# pack.net
KiCad netlist of a schematic drawn in EasyEDA Pro
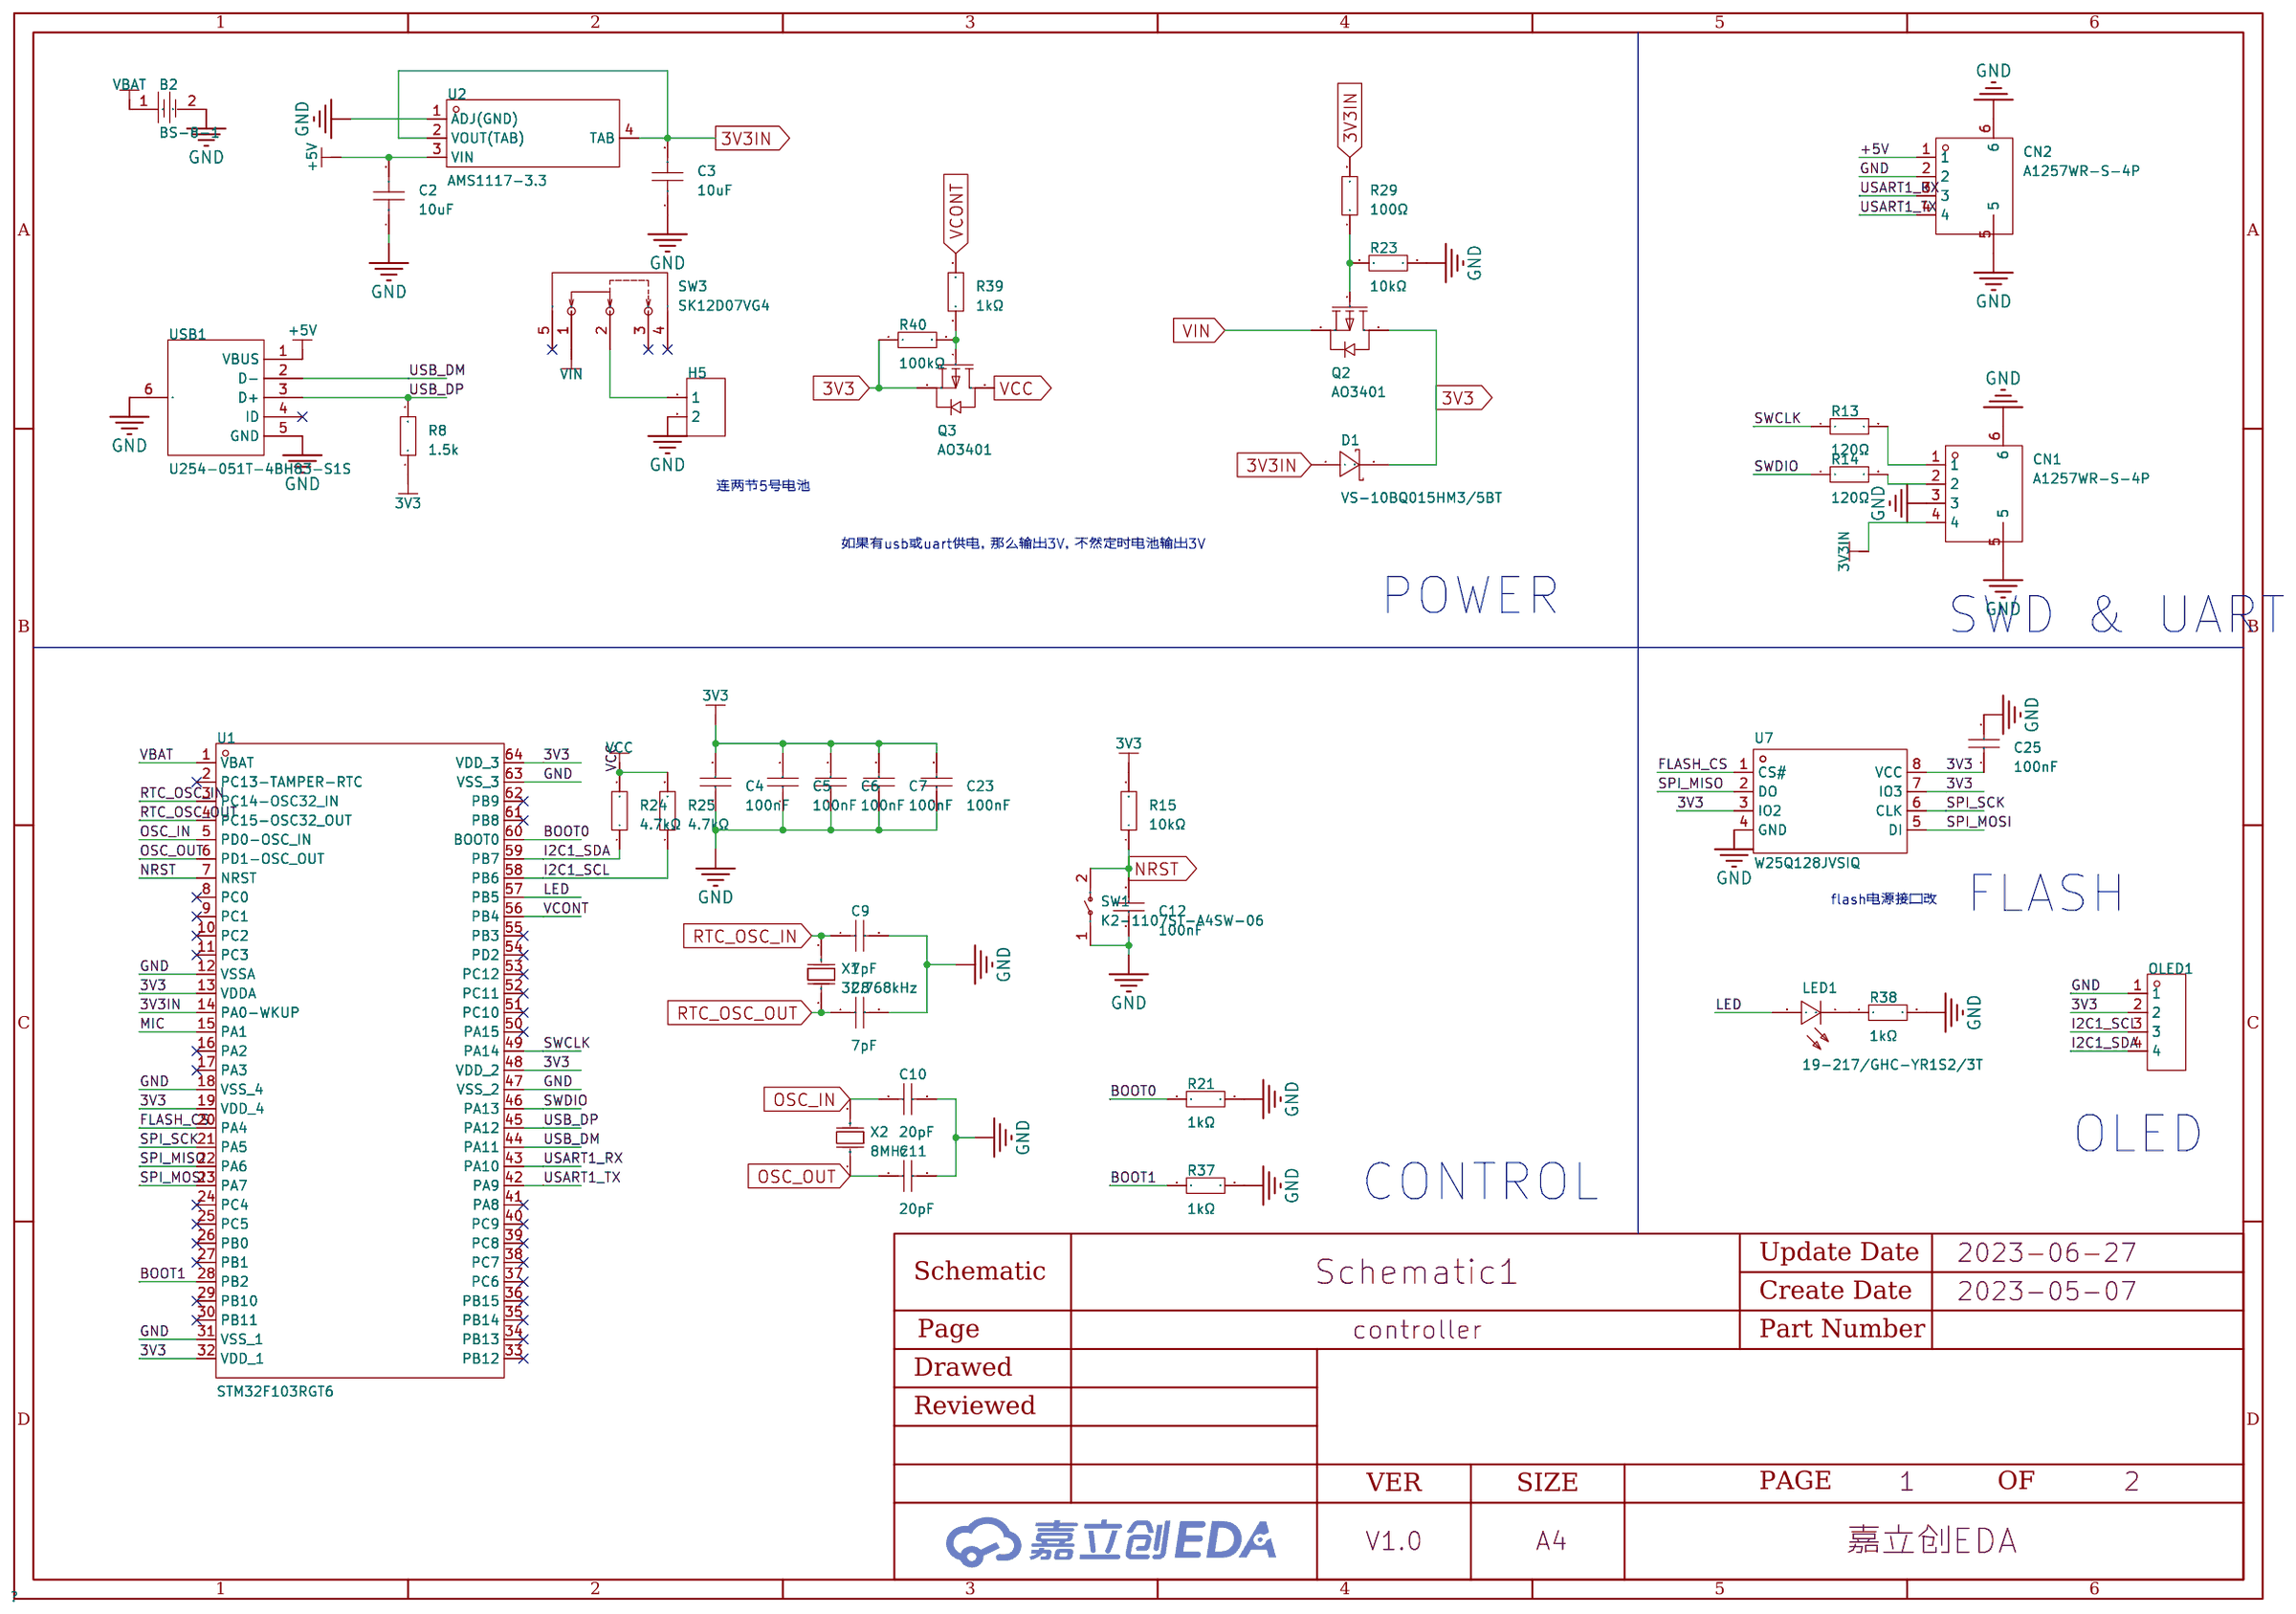
[diagram p0: controller]
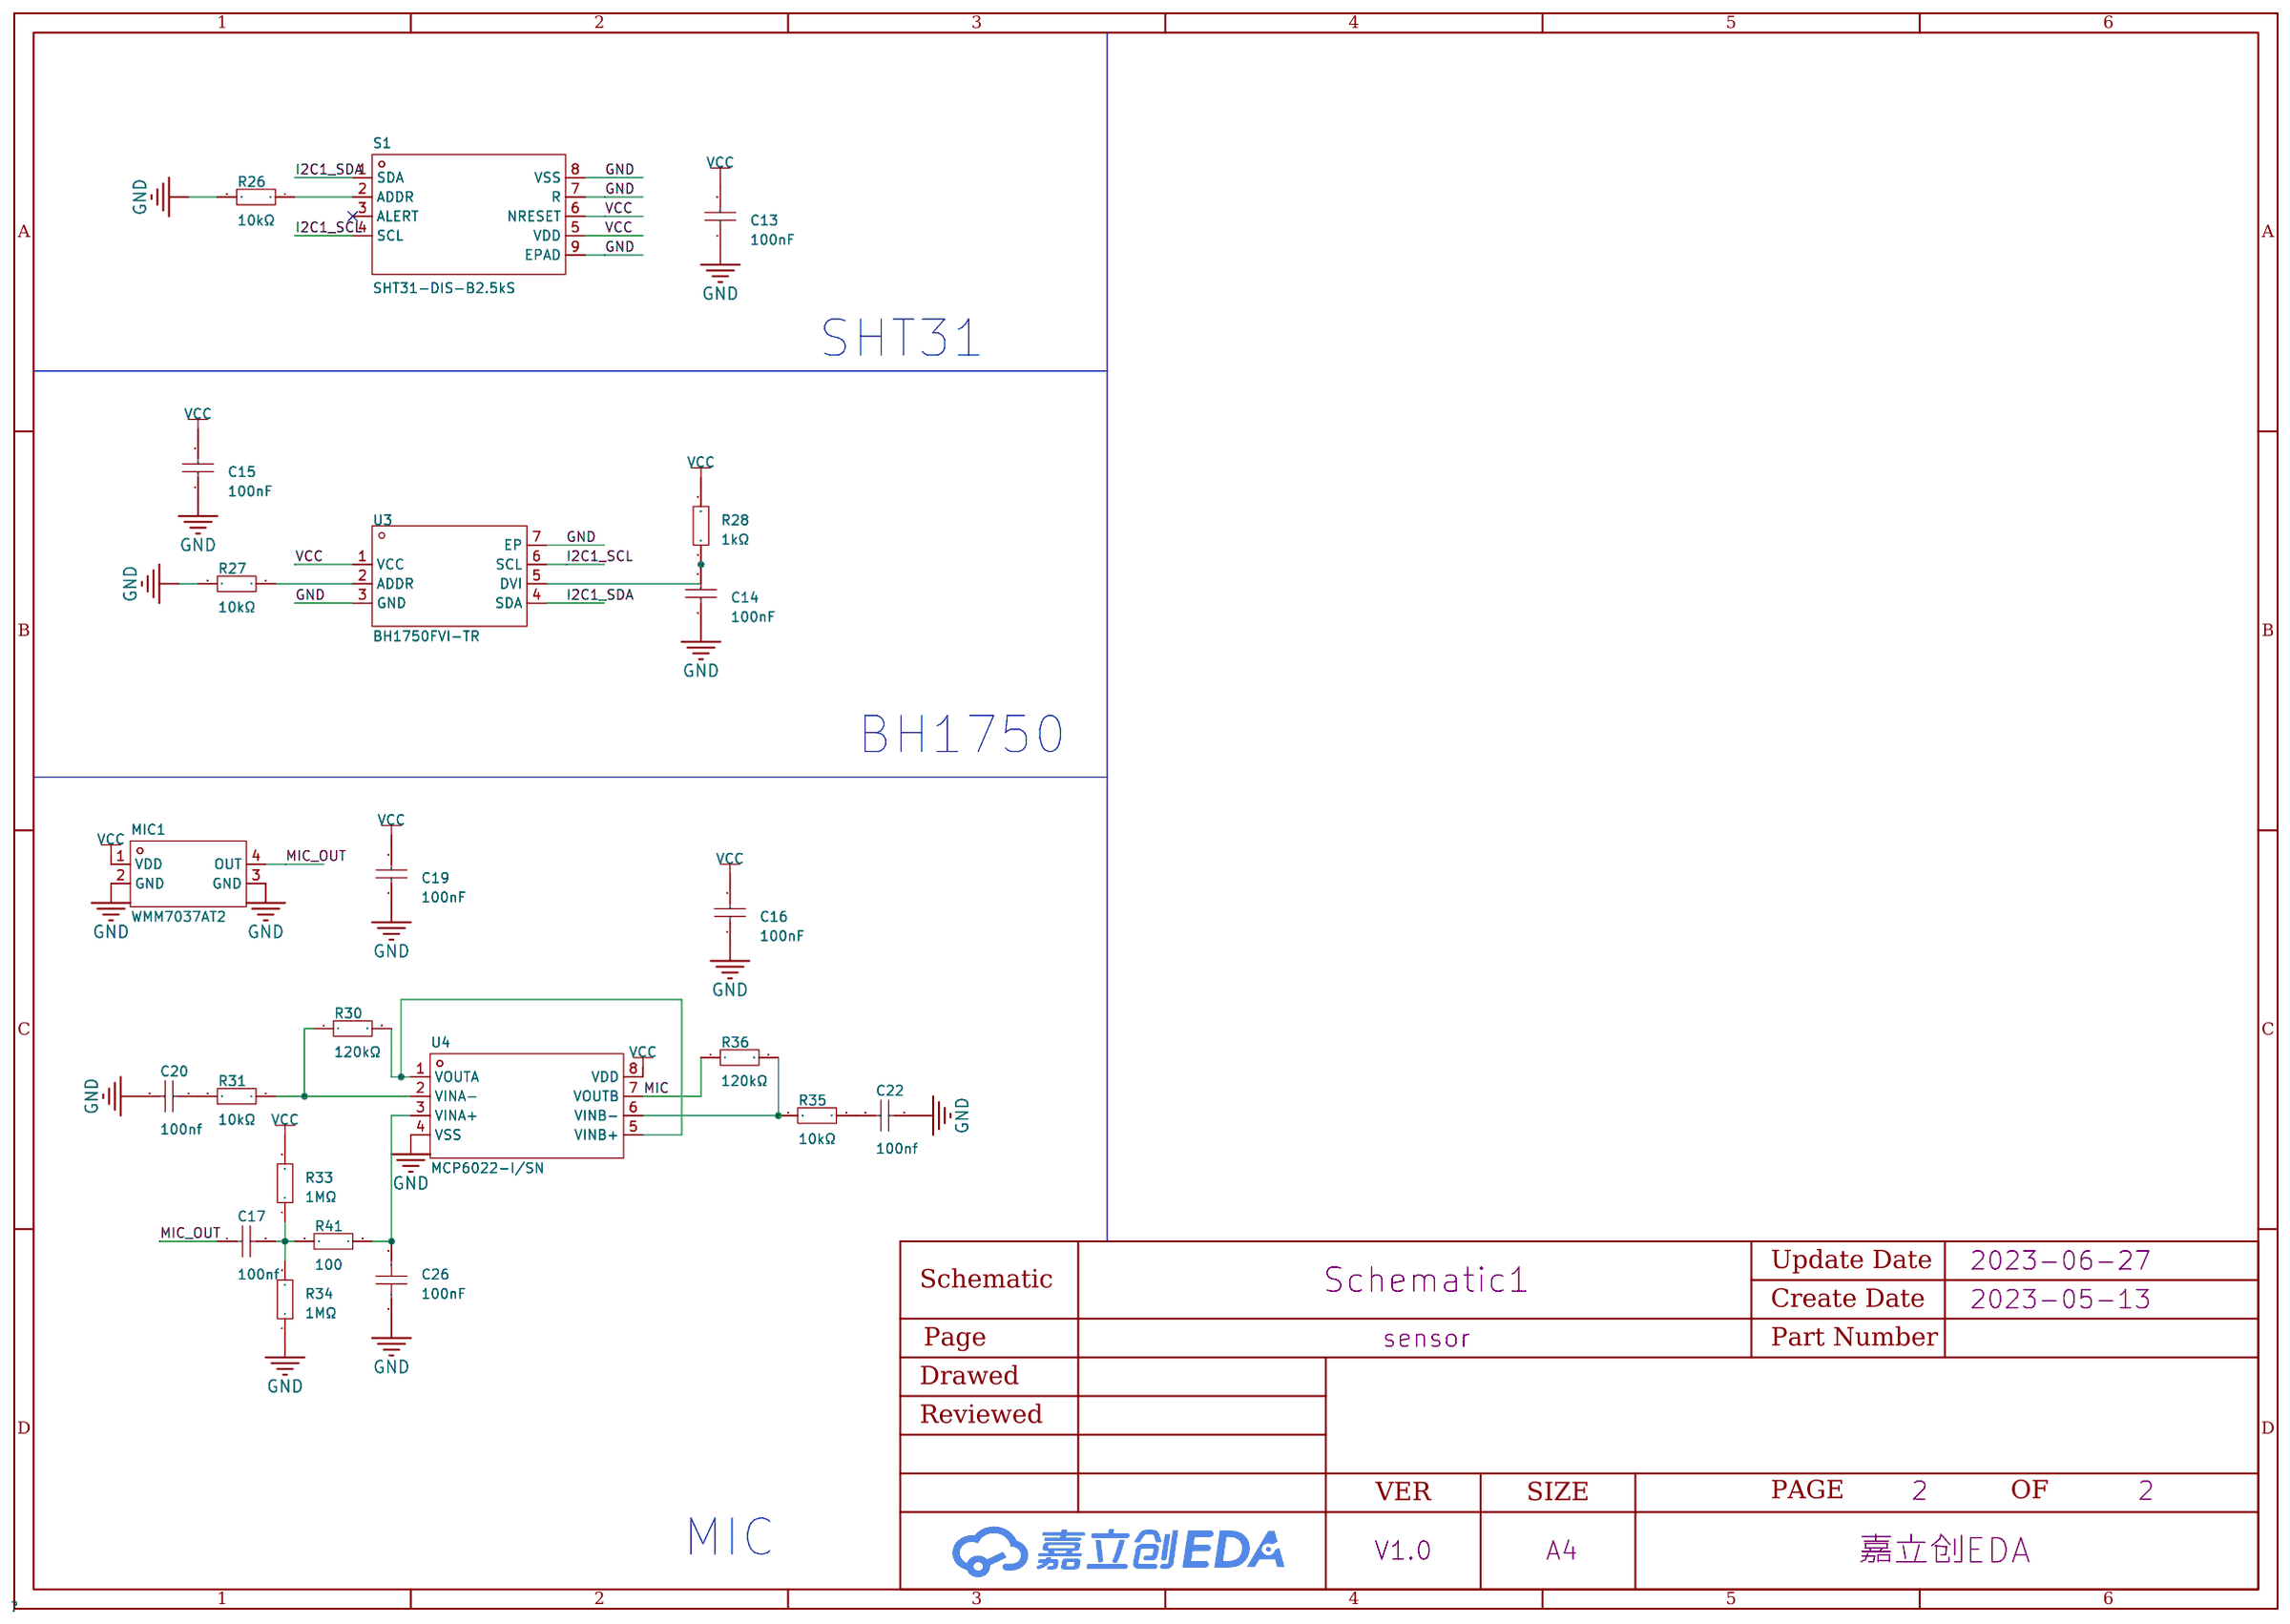
[diagram p1: sensor]

(export (version "E")
  (design (tool "Eeschema 10.0.6"))
  (components
    (comp (ref "B2")
      (value "BS-8-1")
      (footprint "easyedapro:BAT-TH_BS-8-1")
      (description "连接器类型:电池底座;适用电池规格:CR2032;工作温度范围:-55°C~+85°C;")
      (fields (field (name "Manufacturer") "Q&J"))
      (libsource (lib "easyedapro") (part "CR2032-BS-8-1"))
    )
    (comp (ref "C2")
      (value "10uF")
      (footprint "easyedapro:C0603")
      (description "容值:10uF;精度:±20%;额定电压:25V;材质(温度系数):X5R;")
      (fields
        (field (name "Manufacturer Part") "CL10A106MA8NRNC")
        (field (name "Manufacturer") "SAMSUNG(三星)")
      )
      (libsource (lib "easyedapro") (part "CL10A106MA8NRNC"))
    )
    (comp (ref "C3")
      (value "10uF")
      (footprint "easyedapro:C0603")
      (description "容值:10uF;精度:±20%;额定电压:25V;材质(温度系数):X5R;")
      (fields
        (field (name "Manufacturer Part") "CL10A106MA8NRNC")
        (field (name "Manufacturer") "SAMSUNG(三星)")
      )
      (libsource (lib "easyedapro") (part "CL10A106MA8NRNC"))
    )
    (comp (ref "C4")
      (value "100nF")
      (footprint "easyedapro:C0603")
      (description "容值:100nF;精度:±10%;额定电压:50V;材质(温度系数):X7R;")
      (fields (field (name "Manufacturer Part") "0603B104K500NT") (field (name "Manufacturer") "FH(风华)"))
      (libsource (lib "easyedapro") (part "0603B104K500NT"))
    )
    (comp (ref "C5")
      (value "100nF")
      (footprint "easyedapro:C0603")
      (description "容值:100nF;精度:±10%;额定电压:50V;材质(温度系数):X7R;")
      (fields (field (name "Manufacturer Part") "0603B104K500NT") (field (name "Manufacturer") "FH(风华)"))
      (libsource (lib "easyedapro") (part "0603B104K500NT"))
    )
    (comp (ref "C6")
      (value "100nF")
      (footprint "easyedapro:C0603")
      (description "容值:100nF;精度:±10%;额定电压:50V;材质(温度系数):X7R;")
      (fields (field (name "Manufacturer Part") "0603B104K500NT") (field (name "Manufacturer") "FH(风华)"))
      (libsource (lib "easyedapro") (part "0603B104K500NT"))
    )
    (comp (ref "C7")
      (value "100nF")
      (footprint "easyedapro:C0603")
      (description "容值:100nF;精度:±10%;额定电压:50V;材质(温度系数):X7R;")
      (fields (field (name "Manufacturer Part") "0603B104K500NT") (field (name "Manufacturer") "FH(风华)"))
      (libsource (lib "easyedapro") (part "0603B104K500NT"))
    )
    (comp (ref "C8")
      (value "7pF")
      (footprint "easyedapro:C0603")
      (description "容值:7pF;额定电压:50V;材质(温度系数):C0G;")
      (fields (field (name "Manufacturer Part") "0603CG7R0C500NT") (field (name "Manufacturer") "FH(风华)"))
      (libsource (lib "easyedapro") (part "0603CG7R0C500NT"))
    )
    (comp (ref "C9")
      (value "7pF")
      (footprint "easyedapro:C0603")
      (description "容值:7pF;额定电压:50V;材质(温度系数):C0G;")
      (fields (field (name "Manufacturer Part") "0603CG7R0C500NT") (field (name "Manufacturer") "FH(风华)"))
      (libsource (lib "easyedapro") (part "0603CG7R0C500NT"))
    )
    (comp (ref "C10")
      (value "20pF")
      (footprint "easyedapro:C0603")
      (description "容值:20pF;精度:±5%;额定电压:50V;材质(温度系数):C0G;")
      (fields
        (field (name "Manufacturer Part") "CL10C200JB8NNNC")
        (field (name "Manufacturer") "SAMSUNG(三星)")
      )
      (libsource (lib "easyedapro") (part "CL10C200JB8NNNC"))
    )
    (comp (ref "C11")
      (value "20pF")
      (footprint "easyedapro:C0603")
      (description "容值:20pF;精度:±5%;额定电压:50V;材质(温度系数):C0G;")
      (fields
        (field (name "Manufacturer Part") "CL10C200JB8NNNC")
        (field (name "Manufacturer") "SAMSUNG(三星)")
      )
      (libsource (lib "easyedapro") (part "CL10C200JB8NNNC"))
    )
    (comp (ref "C12")
      (value "100nF")
      (footprint "easyedapro:C0603")
      (description "容值:100nF;精度:±10%;额定电压:50V;材质(温度系数):X7R;")
      (fields (field (name "Manufacturer Part") "0603B104K500NT") (field (name "Manufacturer") "FH(风华)"))
      (libsource (lib "easyedapro") (part "0603B104K500NT"))
    )
    (comp (ref "C23")
      (value "100nF")
      (footprint "easyedapro:C0603")
      (description "容值:100nF;精度:±10%;额定电压:50V;材质(温度系数):X7R;")
      (fields (field (name "Manufacturer Part") "0603B104K500NT") (field (name "Manufacturer") "FH(风华)"))
      (libsource (lib "easyedapro") (part "0603B104K500NT"))
    )
    (comp (ref "C25")
      (value "100nF")
      (footprint "easyedapro:C0603")
      (description "容值:100nF;精度:±10%;额定电压:50V;材质(温度系数):X7R;")
      (fields (field (name "Manufacturer Part") "0603B104K500NT") (field (name "Manufacturer") "FH(风华)"))
      (libsource (lib "easyedapro") (part "0603B104K500NT"))
    )
    (comp (ref "CN1")
      (value "A1257WR-S-4P")
      (footprint "easyedapro:CONN-SMD_A1257WR-S-4P")
      (description "参考系列:GH;间距:1.25mm;插针结构:1x4P;排数:1;每排PIN数:4;行距:-;安装方式:-;触头材质:黄铜;")
      (fields (field (name "Manufacturer") "CJT(长江连接器)"))
      (libsource (lib "easyedapro") (part "A1257WR-S-4P"))
    )
    (comp (ref "CN2")
      (value "A1257WR-S-4P")
      (footprint "easyedapro:CONN-SMD_A1257WR-S-4P")
      (description "参考系列:GH;间距:1.25mm;插针结构:1x4P;排数:1;每排PIN数:4;行距:-;安装方式:-;触头材质:黄铜;")
      (fields (field (name "Manufacturer") "CJT(长江连接器)"))
      (libsource (lib "easyedapro") (part "A1257WR-S-4P"))
    )
    (comp (ref "D1")
      (value "VS-10BQ015HM3/5BT")
      (footprint "easyedapro:SMB_L4.6-W3.6-LS5.3-RD")
      (description "直流反向耐压(Vr):15V;平均整流电流(Io):1A;正向压降(Vf):210mV@1A;")
      (fields (field (name "Manufacturer") "VISHAY(威世)"))
      (libsource (lib "easyedapro") (part "VS-10BQ015HM3/5BT"))
    )
    (comp (ref "H5")
      (value "~")
      (footprint "easyedapro:HDR-TH_2P-P2.54-V-F")
      (libsource (lib "easyedapro") (part "Header-Female-2.54_1x2"))
    )
    (comp (ref "LED1")
      (value "19-217/GHC-YR1S2/3T")
      (footprint "easyedapro:LED0603-RD")
      (description "发光颜色:翠绿;二极管配置:-;主波长:520nm~535nm;色温:-;功率:110mW;安装方式:-;")
      (fields (field (name "Manufacturer") "EVERLIGHT(亿光)"))
      (libsource (lib "easyedapro") (part "19-217/GHC-YR1S2/3T"))
    )
    (comp (ref "OLED1")
      (value "~")
      (footprint "easyedapro:HDR-TH_4P-P2.54-V-F")
      (libsource (lib "easyedapro") (part "2.54-1*4P母"))
    )
    (comp (ref "Q2")
      (value "AO3401")
      (footprint "easyedapro:SOT-23-3_L2.9-W1.4-P1.90-LS2.6-BR")
      (description "类型:P沟道;漏源电压(Vdss):30V;连续漏极电流(Id):4.2A;功率(Pd):350mW;导通电阻(RDS(on)@Vgs,Id):65mΩ@10V,4.2A;")
      (fields (field (name "Manufacturer") "TWGMC(台湾迪嘉)"))
      (libsource (lib "easyedapro") (part "AO3401_C727156"))
    )
    (comp (ref "Q3")
      (value "AO3401")
      (footprint "easyedapro:SOT-23-3_L2.9-W1.4-P1.90-LS2.6-BR")
      (description "类型:P沟道;漏源电压(Vdss):30V;连续漏极电流(Id):4.2A;功率(Pd):350mW;导通电阻(RDS(on)@Vgs,Id):65mΩ@10V,4.2A;")
      (fields (field (name "Manufacturer") "TWGMC(台湾迪嘉)"))
      (libsource (lib "easyedapro") (part "AO3401_C727156"))
    )
    (comp (ref "R8")
      (value "1.5k")
      (footprint "easyedapro:R0603")
      (description "电阻类型:厚膜电阻;阻值:4.7kΩ;精度:±1%;功率:100mW;")
      (fields
        (field (name "Manufacturer Part") "0603WAF4701T5E")
        (field (name "Manufacturer") "UNI-ROYAL(厚声)")
      )
      (libsource (lib "easyedapro") (part "0603WAF4701T5E"))
    )
    (comp (ref "R13")
      (value "120Ω")
      (footprint "easyedapro:R0603")
      (description "电阻类型:厚膜电阻;阻值:120Ω;精度:±1%;功率:100mW;")
      (fields
        (field (name "Manufacturer Part") "0603WAF1200T5E")
        (field (name "Manufacturer") "UNI-ROYAL(厚声)")
      )
      (libsource (lib "easyedapro") (part "0603WAF1200T5E"))
    )
    (comp (ref "R14")
      (value "120Ω")
      (footprint "easyedapro:R0603")
      (description "电阻类型:厚膜电阻;阻值:120Ω;精度:±1%;功率:100mW;")
      (fields
        (field (name "Manufacturer Part") "0603WAF1200T5E")
        (field (name "Manufacturer") "UNI-ROYAL(厚声)")
      )
      (libsource (lib "easyedapro") (part "0603WAF1200T5E"))
    )
    (comp (ref "R15")
      (value "10kΩ")
      (footprint "easyedapro:R0603")
      (description "电阻类型:厚膜电阻;阻值:10kΩ;精度:±1%;功率:100mW;")
      (fields
        (field (name "Manufacturer Part") "0603WAF1002T5E")
        (field (name "Manufacturer") "UNI-ROYAL(厚声)")
      )
      (libsource (lib "easyedapro") (part "0603WAF1002T5E"))
    )
    (comp (ref "R21")
      (value "1kΩ")
      (footprint "easyedapro:R0603")
      (description "电阻类型:厚膜电阻;阻值:1kΩ;精度:±1%;功率:100mW;")
      (fields
        (field (name "Manufacturer Part") "0603WAF1001T5E")
        (field (name "Manufacturer") "UNI-ROYAL(厚声)")
      )
      (libsource (lib "easyedapro") (part "0603WAF1001T5E"))
    )
    (comp (ref "R23")
      (value "10kΩ")
      (footprint "easyedapro:R0603")
      (description "电阻类型:厚膜电阻;阻值:10kΩ;精度:±1%;功率:100mW;")
      (fields
        (field (name "Manufacturer Part") "0603WAF1002T5E")
        (field (name "Manufacturer") "UNI-ROYAL(厚声)")
      )
      (libsource (lib "easyedapro") (part "0603WAF1002T5E"))
    )
    (comp (ref "R24")
      (value "4.7kΩ")
      (footprint "easyedapro:R0603")
      (description "电阻类型:厚膜电阻;阻值:4.7kΩ;精度:±1%;功率:100mW;")
      (fields
        (field (name "Manufacturer Part") "0603WAF4701T5E")
        (field (name "Manufacturer") "UNI-ROYAL(厚声)")
      )
      (libsource (lib "easyedapro") (part "0603WAF4701T5E"))
    )
    (comp (ref "R25")
      (value "4.7kΩ")
      (footprint "easyedapro:R0603")
      (description "电阻类型:厚膜电阻;阻值:4.7kΩ;精度:±1%;功率:100mW;")
      (fields
        (field (name "Manufacturer Part") "0603WAF4701T5E")
        (field (name "Manufacturer") "UNI-ROYAL(厚声)")
      )
      (libsource (lib "easyedapro") (part "0603WAF4701T5E"))
    )
    (comp (ref "R29")
      (value "100Ω")
      (footprint "easyedapro:R0603")
      (description "电阻类型:厚膜电阻;阻值:100Ω;精度:±1%;功率:100mW;")
      (fields
        (field (name "Manufacturer Part") "0603WAF1000T5E")
        (field (name "Manufacturer") "UNI-ROYAL(厚声)")
      )
      (libsource (lib "easyedapro") (part "0603WAF1000T5E"))
    )
    (comp (ref "R37")
      (value "1kΩ")
      (footprint "easyedapro:R0603")
      (description "电阻类型:厚膜电阻;阻值:1kΩ;精度:±1%;功率:100mW;")
      (fields
        (field (name "Manufacturer Part") "0603WAF1001T5E")
        (field (name "Manufacturer") "UNI-ROYAL(厚声)")
      )
      (libsource (lib "easyedapro") (part "0603WAF1001T5E"))
    )
    (comp (ref "R38")
      (value "1kΩ")
      (footprint "easyedapro:R0603")
      (description "电阻类型:厚膜电阻;阻值:1kΩ;精度:±1%;功率:100mW;")
      (fields
        (field (name "Manufacturer Part") "0603WAF1001T5E")
        (field (name "Manufacturer") "UNI-ROYAL(厚声)")
      )
      (libsource (lib "easyedapro") (part "0603WAF1001T5E"))
    )
    (comp (ref "R39")
      (value "1kΩ")
      (footprint "easyedapro:R0603")
      (description "电阻类型:厚膜电阻;阻值:1kΩ;精度:±1%;功率:100mW;")
      (fields
        (field (name "Manufacturer Part") "0603WAF1001T5E")
        (field (name "Manufacturer") "UNI-ROYAL(厚声)")
      )
      (libsource (lib "easyedapro") (part "0603WAF1001T5E"))
    )
    (comp (ref "R40")
      (value "100kΩ")
      (footprint "easyedapro:R0603")
      (description "电阻类型:厚膜电阻;阻值:100kΩ;精度:±1%;功率:100mW;")
      (fields
        (field (name "Manufacturer Part") "0603WAF1003T5E")
        (field (name "Manufacturer") "UNI-ROYAL(厚声)")
      )
      (libsource (lib "easyedapro") (part "0603WAF1003T5E"))
    )
    (comp (ref "SW1")
      (value "K2-1107ST-A4SW-06")
      (footprint "easyedapro:SW-SMD_L6.1-W3.6-LS7.9")
      (fields (field (name "Manufacturer") "韩国韩荣"))
      (libsource (lib "easyedapro") (part "K2-1107ST-A4SW-06_C2837195"))
    )
    (comp (ref "SW3")
      (value "SK12D07VG4")
      (footprint "easyedapro:SW-TH_SK12D07VG4")
      (description "额定电压 DC:50V;触点额定电流:500mA @ 50VDC;电路结构:SPDT;额定电压 AC:-;开关功能:On-On;")
      (fields (field (name "Manufacturer") "SHOU HAN(首韩)"))
      (libsource (lib "easyedapro") (part "SK12D07VG4"))
    )
    (comp (ref "U1")
      (value "STM32F103RGT6")
      (footprint "easyedapro:LQFP-64_L10.0-W10.0-P0.50-LS12.0-BL")
      (description "CPU内核:ARM Cortex-M3;CPU最大主频:72MHz;程序存储容量:1MB;程序存储器类型:FLASH;RAM总容量:96KB;GPIO端口数量:51;")
      (fields (field (name "Manufacturer") "ST(意法半导体)"))
      (libsource (lib "easyedapro") (part "STM32F103RGT6"))
    )
    (comp (ref "U2")
      (value "AMS1117-3.3")
      (footprint "easyedapro:SOT-223-4_L6.5-W3.5-P2.30-LS7.0-BR")
      (description "输出类型:固定;输出极性:正;最大输入电压:18V;输出电压:3.3V;输出电流:1A;电源纹波抑制比(PSRR):60dB@(120Hz);")
      (fields (field (name "Manufacturer") "UMW(广东友台半导体)"))
      (libsource (lib "easyedapro") (part "AMS1117-3.3_C347222"))
    )
    (comp (ref "U7")
      (value "W25Q128JVSIQ")
      (footprint "easyedapro:SOIC-8_L5.3-W5.3-P1.27-LS8.0-BL")
      (description "128Mbit(16MBx8bit),高速版,133MHz(266/532MHz Dual/Quad-SPI,66MB/S),比W25Q128FVSIG,W25Q128FVFIG更高速")
      (fields (field (name "Manufacturer") "WINBOND(华邦)"))
      (libsource (lib "easyedapro") (part "W25Q128JVSIQTR"))
    )
    (comp (ref "USB1")
      (value "U254-051T-4BH83-S1S")
      (footprint "easyedapro:MICRO-USB-SMD_U254-051T-4BH83-S1S")
      (fields (field (name "Manufacturer") "XKB Connectivity(中国星坤)"))
      (libsource (lib "easyedapro") (part "U254-051T-4BH83-S1S"))
    )
    (comp (ref "X1")
      (value "32.768kHz")
      (footprint "easyedapro:FC-12M_L2.0-W1.2")
      (description "频率:32.768kHz;频率公差:±20ppm;负载电容:7pF;")
      (fields
        (field (name "Manufacturer Part") "FC-12M32.768KHZ7PF20PPM")
        (field (name "Manufacturer") "EPSON(爱普生)")
      )
      (libsource (lib "easyedapro") (part "FC-12M32.768KHZ7PF20PPM"))
    )
    (comp (ref "X2")
      (value "8MHz")
      (footprint "easyedapro:CRYSTAL-SMD_L5.0-W3.2")
      (description "频率:8MHz;频率公差:±10ppm;负载电容:20pF;")
      (fields (field (name "Manufacturer Part") "X50328MSB2GI") (field (name "Manufacturer") "YXC(扬兴晶振)"))
      (libsource (lib "easyedapro") (part "X50328MSB2GI"))
    )
    (comp (ref "C13")
      (value "100nF")
      (footprint "easyedapro:C0603")
      (description "容值:100nF;精度:±10%;额定电压:50V;材质(温度系数):X7R;")
      (fields (field (name "Manufacturer Part") "0603B104K500NT") (field (name "Manufacturer") "FH(风华)"))
      (libsource (lib "easyedapro") (part "0603B104K500NT"))
    )
    (comp (ref "C14")
      (value "100nF")
      (footprint "easyedapro:C0603")
      (description "容值:100nF;精度:±10%;额定电压:50V;材质(温度系数):X7R;")
      (fields (field (name "Manufacturer Part") "0603B104K500NT") (field (name "Manufacturer") "FH(风华)"))
      (libsource (lib "easyedapro") (part "0603B104K500NT"))
    )
    (comp (ref "C15")
      (value "100nF")
      (footprint "easyedapro:C0603")
      (description "容值:100nF;精度:±10%;额定电压:50V;材质(温度系数):X7R;")
      (fields (field (name "Manufacturer Part") "0603B104K500NT") (field (name "Manufacturer") "FH(风华)"))
      (libsource (lib "easyedapro") (part "0603B104K500NT"))
    )
    (comp (ref "C16")
      (value "100nF")
      (footprint "easyedapro:C0603")
      (description "容值:100nF;精度:±10%;额定电压:50V;材质(温度系数):X7R;")
      (fields (field (name "Manufacturer Part") "0603B104K500NT") (field (name "Manufacturer") "FH(风华)"))
      (libsource (lib "easyedapro") (part "0603B104K500NT"))
    )
    (comp (ref "C17")
      (value "100nf")
      (footprint "easyedapro:C0603")
      (description "容值:1uF;精度:±10%;额定电压:50V;材质(温度系数):X5R;")
      (fields
        (field (name "Manufacturer Part") "CL10A105KB8NNNC")
        (field (name "Manufacturer") "SAMSUNG(三星)")
      )
      (libsource (lib "easyedapro") (part "CL10A105KB8NNNC"))
    )
    (comp (ref "C19")
      (value "100nF")
      (footprint "easyedapro:C0603")
      (description "容值:100nF;精度:±10%;额定电压:50V;材质(温度系数):X7R;")
      (fields (field (name "Manufacturer Part") "0603B104K500NT") (field (name "Manufacturer") "FH(风华)"))
      (libsource (lib "easyedapro") (part "0603B104K500NT"))
    )
    (comp (ref "C20")
      (value "100nf")
      (footprint "easyedapro:C0603")
      (description "容值:100nF;精度:±10%;额定电压:50V;材质(温度系数):X7R;")
      (fields (field (name "Manufacturer Part") "0603B104K500NT") (field (name "Manufacturer") "FH(风华)"))
      (libsource (lib "easyedapro") (part "0603B104K500NT"))
    )
    (comp (ref "C22")
      (value "100nf")
      (footprint "easyedapro:C0603")
      (description "容值:100nF;精度:±10%;额定电压:50V;材质(温度系数):X7R;")
      (fields (field (name "Manufacturer Part") "0603B104K500NT") (field (name "Manufacturer") "FH(风华)"))
      (libsource (lib "easyedapro") (part "0603B104K500NT"))
    )
    (comp (ref "C26")
      (value "100nF")
      (footprint "easyedapro:C0603")
      (libsource (lib "easyedapro") (part "CapAcitance"))
    )
    (comp (ref "MIC1")
      (value "WMM7037AT2")
      (footprint "easyedapro:MIC-SMD_L3.8-W3.00-TL")
      (description "方向:全指向;灵敏度:-42dB;信噪比:59dB;电流消耗:80uA;电源电压:1.5V~3.6V;阻抗:200Ω;")
      (fields (field (name "Manufacturer") "WILLSEMI(韦尔)"))
      (libsource (lib "easyedapro") (part "WMM7037AT2"))
    )
    (comp (ref "R26")
      (value "10kΩ")
      (footprint "easyedapro:R0603")
      (description "电阻类型:厚膜电阻;阻值:10kΩ;精度:±1%;功率:100mW;")
      (fields
        (field (name "Manufacturer Part") "0603WAF1002T5E")
        (field (name "Manufacturer") "UNI-ROYAL(厚声)")
      )
      (libsource (lib "easyedapro") (part "0603WAF1002T5E"))
    )
    (comp (ref "R27")
      (value "10kΩ")
      (footprint "easyedapro:R0603")
      (description "电阻类型:厚膜电阻;阻值:10kΩ;精度:±1%;功率:100mW;")
      (fields
        (field (name "Manufacturer Part") "0603WAF1002T5E")
        (field (name "Manufacturer") "UNI-ROYAL(厚声)")
      )
      (libsource (lib "easyedapro") (part "0603WAF1002T5E"))
    )
    (comp (ref "R28")
      (value "1kΩ")
      (footprint "easyedapro:R0603")
      (description "电阻类型:厚膜电阻;阻值:1kΩ;精度:±1%;功率:100mW;")
      (fields
        (field (name "Manufacturer Part") "0603WAF1001T5E")
        (field (name "Manufacturer") "UNI-ROYAL(厚声)")
      )
      (libsource (lib "easyedapro") (part "0603WAF1001T5E"))
    )
    (comp (ref "R30")
      (value "120kΩ")
      (footprint "easyedapro:R0603")
      (description "电阻类型:厚膜电阻;阻值:120kΩ;精度:±1%;功率:100mW;")
      (fields
        (field (name "Manufacturer Part") "0603WAF1203T5E")
        (field (name "Manufacturer") "UNI-ROYAL(厚声)")
      )
      (libsource (lib "easyedapro") (part "0603WAF1203T5E"))
    )
    (comp (ref "R31")
      (value "10kΩ")
      (footprint "easyedapro:R0603")
      (description "电阻类型:厚膜电阻;阻值:10kΩ;精度:±1%;功率:100mW;")
      (fields
        (field (name "Manufacturer Part") "0603WAF1002T5E")
        (field (name "Manufacturer") "UNI-ROYAL(厚声)")
      )
      (libsource (lib "easyedapro") (part "0603WAF1002T5E"))
    )
    (comp (ref "R33")
      (value "1MΩ")
      (footprint "easyedapro:R0603")
      (description "电阻类型:厚膜电阻;阻值:1MΩ;精度:±1%;功率:100mW;")
      (fields
        (field (name "Manufacturer Part") "0603WAF1004T5E")
        (field (name "Manufacturer") "UNI-ROYAL(厚声)")
      )
      (libsource (lib "easyedapro") (part "0603WAF1004T5E"))
    )
    (comp (ref "R34")
      (value "1MΩ")
      (footprint "easyedapro:R0603")
      (description "电阻类型:厚膜电阻;阻值:1MΩ;精度:±1%;功率:100mW;")
      (fields
        (field (name "Manufacturer Part") "0603WAF1004T5E")
        (field (name "Manufacturer") "UNI-ROYAL(厚声)")
      )
      (libsource (lib "easyedapro") (part "0603WAF1004T5E"))
    )
    (comp (ref "R35")
      (value "10kΩ")
      (footprint "easyedapro:R0603")
      (description "电阻类型:厚膜电阻;阻值:10kΩ;精度:±1%;功率:100mW;")
      (fields
        (field (name "Manufacturer Part") "0603WAF1002T5E")
        (field (name "Manufacturer") "UNI-ROYAL(厚声)")
      )
      (libsource (lib "easyedapro") (part "0603WAF1002T5E"))
    )
    (comp (ref "R36")
      (value "120kΩ")
      (footprint "easyedapro:R0603")
      (description "电阻类型:厚膜电阻;阻值:120kΩ;精度:±1%;功率:100mW;")
      (fields
        (field (name "Manufacturer Part") "0603WAF1203T5E")
        (field (name "Manufacturer") "UNI-ROYAL(厚声)")
      )
      (libsource (lib "easyedapro") (part "0603WAF1203T5E"))
    )
    (comp (ref "R41") (value "100") (footprint "easyedapro:R0603") (libsource (lib "easyedapro") (part "电阻")))
    (comp (ref "S1")
      (value "SHT31-DIS-B2.5kS")
      (footprint "easyedapro:DFN-8_L2.5-W2.5-P0.50-BL-EP")
      (description "数字式温湿度传感器SHT31， RH精度：0-100%全量程典型误差值±2%，比SHT30更高精度，DFN封装，")
      (fields (field (name "Manufacturer") "Sensirion(瑞士盛思锐)"))
      (libsource (lib "easyedapro") (part "SHT31-DIS-B"))
    )
    (comp (ref "U3")
      (value "BH1750FVI-TR")
      (footprint "easyedapro:WSOF-6_L2.6-W1.6-P0.50-TL-EP")
      (description "数字16-bit I2C串行输出，环境光传感器，工作电压：2.4V~3.6V")
      (fields (field (name "Manufacturer") "ROHM(罗姆)"))
      (libsource (lib "easyedapro") (part "BH1750FVI-TR"))
    )
    (comp (ref "U4")
      (value "MCP6022-I/SN")
      (footprint "easyedapro:SOIC-8_L4.9-W3.9-P1.27-LS6.0-BL")
      (description "运放类型:宽带运放;放大器组数:2;增益带宽积（GBP）:10MHz;压摆率（SR）:7 V/us;电源电压:2.5V ~ 5.5V;各通道供电电流:1mA;")
      (fields (field (name "Manufacturer") "MICROCHIP(美国微芯)"))
      (libsource (lib "easyedapro") (part "MCP6022-I/SN"))
    )
  )
  (nets
    (net (code "1") (name "+5V") (class "Default")
      (node (ref "C2") (pin "2") (pinfunction "2_2") (pintype "input"))
      (node (ref "CN2") (pin "1") (pinfunction "1_1") (pintype "input"))
      (node (ref "U2") (pin "3") (pinfunction "VIN_3") (pintype "input"))
      (node (ref "USB1") (pin "1") (pinfunction "VBUS_1") (pintype "input"))
    )
    (net (code "2") (name "3V3") (class "Default")
      (node (ref "C23") (pin "2") (pinfunction "2_2") (pintype "input"))
      (node (ref "C25") (pin "1") (pinfunction "1_1") (pintype "input"))
      (node (ref "C4") (pin "2") (pinfunction "2_2") (pintype "input"))
      (node (ref "C5") (pin "2") (pinfunction "2_2") (pintype "input"))
      (node (ref "C6") (pin "2") (pinfunction "2_2") (pintype "input"))
      (node (ref "C7") (pin "2") (pinfunction "2_2") (pintype "input"))
      (node (ref "D1") (pin "1") (pinfunction "C_1") (pintype "input"))
      (node (ref "OLED1") (pin "2") (pinfunction "2_2") (pintype "input"))
      (node (ref "Q2") (pin "3") (pinfunction "D_3") (pintype "input"))
      (node (ref "Q3") (pin "2") (pinfunction "S_2") (pintype "input"))
      (node (ref "R15") (pin "2") (pinfunction "2_2") (pintype "input"))
      (node (ref "R40") (pin "1") (pinfunction "1_1") (pintype "input"))
      (node (ref "R8") (pin "1") (pinfunction "1_1") (pintype "input"))
      (node (ref "U1") (pin "13") (pinfunction "VDDA_13") (pintype "input"))
      (node (ref "U1") (pin "19") (pinfunction "VDD_4_19") (pintype "input"))
      (node (ref "U1") (pin "32") (pinfunction "VDD_1_32") (pintype "input"))
      (node (ref "U1") (pin "48") (pinfunction "VDD_2_48") (pintype "input"))
      (node (ref "U1") (pin "64") (pinfunction "VDD_3_64") (pintype "input"))
      (node (ref "U7") (pin "3") (pinfunction "IO2_3") (pintype "input"))
      (node (ref "U7") (pin "7") (pinfunction "IO3_7") (pintype "input"))
      (node (ref "U7") (pin "8") (pinfunction "VCC_8") (pintype "input"))
    )
    (net (code "3") (name "3V3IN") (class "Default")
      (node (ref "C3") (pin "2") (pinfunction "2_2") (pintype "input"))
      (node (ref "CN1") (pin "4") (pinfunction "4_4") (pintype "input"))
      (node (ref "D1") (pin "2") (pinfunction "A_2") (pintype "input"))
      (node (ref "R29") (pin "2") (pinfunction "2_2") (pintype "input"))
      (node (ref "U1") (pin "14") (pinfunction "PA0-WKUP_14") (pintype "input"))
      (node (ref "U2") (pin "2") (pinfunction "VOUT(TAB)_2") (pintype "input"))
      (node (ref "U2") (pin "4") (pinfunction "TAB_4") (pintype "input"))
    )
    (net (code "4") (name "BOOT0") (class "Default")
      (node (ref "R21") (pin "1") (pinfunction "1_1") (pintype "input"))
      (node (ref "U1") (pin "60") (pinfunction "BOOT0_60") (pintype "input"))
    )
    (net (code "5") (name "BOOT1") (class "Default")
      (node (ref "R37") (pin "1") (pinfunction "1_1") (pintype "input"))
      (node (ref "U1") (pin "28") (pinfunction "PB2_28") (pintype "input"))
    )
    (net (code "6") (name "FLASH_CS") (class "Default")
      (node (ref "U1") (pin "20") (pinfunction "PA4_20") (pintype "input"))
      (node (ref "U7") (pin "1") (pinfunction "CS#_1") (pintype "input"))
    )
    (net (code "7") (name "GND") (class "Default")
      (node (ref "B2") (pin "2") (pinfunction "2_2") (pintype "input"))
      (node (ref "C10") (pin "2") (pinfunction "2_2") (pintype "input"))
      (node (ref "C11") (pin "2") (pinfunction "2_2") (pintype "input"))
      (node (ref "C12") (pin "1") (pinfunction "1_1") (pintype "input"))
      (node (ref "C13") (pin "1") (pinfunction "1_1") (pintype "input"))
      (node (ref "C14") (pin "1") (pinfunction "1_1") (pintype "input"))
      (node (ref "C15") (pin "1") (pinfunction "1_1") (pintype "input"))
      (node (ref "C16") (pin "1") (pinfunction "1_1") (pintype "input"))
      (node (ref "C19") (pin "1") (pinfunction "1_1") (pintype "input"))
      (node (ref "C2") (pin "1") (pinfunction "1_1") (pintype "input"))
      (node (ref "C20") (pin "2") (pinfunction "2_2") (pintype "input"))
      (node (ref "C22") (pin "2") (pinfunction "2_2") (pintype "input"))
      (node (ref "C23") (pin "1") (pinfunction "1_1") (pintype "input"))
      (node (ref "C25") (pin "2") (pinfunction "2_2") (pintype "input"))
      (node (ref "C26") (pin "1") (pinfunction "1_1") (pintype "input"))
      (node (ref "C3") (pin "1") (pinfunction "1_1") (pintype "input"))
      (node (ref "C4") (pin "1") (pinfunction "1_1") (pintype "input"))
      (node (ref "C5") (pin "1") (pinfunction "1_1") (pintype "input"))
      (node (ref "C6") (pin "1") (pinfunction "1_1") (pintype "input"))
      (node (ref "C7") (pin "1") (pinfunction "1_1") (pintype "input"))
      (node (ref "C8") (pin "2") (pinfunction "2_2") (pintype "input"))
      (node (ref "C9") (pin "2") (pinfunction "2_2") (pintype "input"))
      (node (ref "CN1") (pin "3") (pinfunction "3_3") (pintype "input"))
      (node (ref "CN1") (pin "5") (pinfunction "5_5") (pintype "input"))
      (node (ref "CN1") (pin "6") (pinfunction "6_6") (pintype "input"))
      (node (ref "CN2") (pin "2") (pinfunction "2_2") (pintype "input"))
      (node (ref "CN2") (pin "5") (pinfunction "5_5") (pintype "input"))
      (node (ref "CN2") (pin "6") (pinfunction "6_6") (pintype "input"))
      (node (ref "H5") (pin "2") (pinfunction "2_2") (pintype "input"))
      (node (ref "MIC1") (pin "2") (pinfunction "GND_2") (pintype "input"))
      (node (ref "MIC1") (pin "3") (pinfunction "GND_3") (pintype "input"))
      (node (ref "OLED1") (pin "1") (pinfunction "1_1") (pintype "input"))
      (node (ref "R21") (pin "2") (pinfunction "2_2") (pintype "input"))
      (node (ref "R23") (pin "1") (pinfunction "1_1") (pintype "input"))
      (node (ref "R26") (pin "2") (pinfunction "2_2") (pintype "input"))
      (node (ref "R27") (pin "2") (pinfunction "2_2") (pintype "input"))
      (node (ref "R34") (pin "1") (pinfunction "1_1") (pintype "input"))
      (node (ref "R37") (pin "2") (pinfunction "2_2") (pintype "input"))
      (node (ref "R38") (pin "2") (pinfunction "2_2") (pintype "input"))
      (node (ref "S1") (pin "7") (pinfunction "R_7") (pintype "input"))
      (node (ref "S1") (pin "8") (pinfunction "VSS_8") (pintype "input"))
      (node (ref "S1") (pin "9") (pinfunction "EPAD_9") (pintype "input"))
      (node (ref "SW1") (pin "1") (pinfunction "1_1") (pintype "input"))
      (node (ref "U1") (pin "12") (pinfunction "VSSA_12") (pintype "input"))
      (node (ref "U1") (pin "18") (pinfunction "VSS_4_18") (pintype "input"))
      (node (ref "U1") (pin "31") (pinfunction "VSS_1_31") (pintype "input"))
      (node (ref "U1") (pin "47") (pinfunction "VSS_2_47") (pintype "input"))
      (node (ref "U1") (pin "63") (pinfunction "VSS_3_63") (pintype "input"))
      (node (ref "U2") (pin "1") (pinfunction "ADJ(GND)_1") (pintype "input"))
      (node (ref "U3") (pin "3") (pinfunction "GND_3") (pintype "input"))
      (node (ref "U3") (pin "7") (pinfunction "EP_7") (pintype "input"))
      (node (ref "U4") (pin "4") (pinfunction "VSS_4") (pintype "input"))
      (node (ref "U7") (pin "4") (pinfunction "GND_4") (pintype "input"))
      (node (ref "USB1") (pin "5") (pinfunction "GND_5") (pintype "input"))
      (node (ref "USB1") (pin "6") (pinfunction "EH_6") (pintype "input"))
    )
    (net (code "8") (name "I2C1_SCL") (class "Default")
      (node (ref "OLED1") (pin "3") (pinfunction "3_3") (pintype "input"))
      (node (ref "R25") (pin "1") (pinfunction "1_1") (pintype "input"))
      (node (ref "S1") (pin "4") (pinfunction "SCL_4") (pintype "input"))
      (node (ref "U1") (pin "58") (pinfunction "PB6_58") (pintype "input"))
      (node (ref "U3") (pin "6") (pinfunction "SCL_6") (pintype "input"))
    )
    (net (code "9") (name "I2C1_SDA") (class "Default")
      (node (ref "OLED1") (pin "4") (pinfunction "4_4") (pintype "input"))
      (node (ref "R24") (pin "1") (pinfunction "1_1") (pintype "input"))
      (node (ref "S1") (pin "1") (pinfunction "SDA_1") (pintype "input"))
      (node (ref "U1") (pin "59") (pinfunction "PB7_59") (pintype "input"))
      (node (ref "U3") (pin "4") (pinfunction "SDA_4") (pintype "input"))
    )
    (net (code "10") (name "LED") (class "Default")
      (node (ref "LED1") (pin "2") (pinfunction "A_2") (pintype "input"))
      (node (ref "U1") (pin "57") (pinfunction "PB5_57") (pintype "input"))
    )
    (net (code "11") (name "MIC") (class "Default")
      (node (ref "R36") (pin "1") (pinfunction "1_1") (pintype "input"))
      (node (ref "U1") (pin "15") (pinfunction "PA1_15") (pintype "input"))
      (node (ref "U4") (pin "7") (pinfunction "VOUTB_7") (pintype "input"))
    )
    (net (code "12") (name "MIC_OUT") (class "Default")
      (node (ref "C17") (pin "1") (pinfunction "1_1") (pintype "input"))
      (node (ref "MIC1") (pin "4") (pinfunction "OUT_4") (pintype "input"))
    )
    (net (code "13") (name "NRST") (class "Default")
      (node (ref "C12") (pin "2") (pinfunction "2_2") (pintype "input"))
      (node (ref "R15") (pin "1") (pinfunction "1_1") (pintype "input"))
      (node (ref "SW1") (pin "2") (pinfunction "2_2") (pintype "input"))
      (node (ref "U1") (pin "7") (pinfunction "NRST_7") (pintype "input"))
    )
    (net (code "14") (name "Net-(C17-Pad2)") (class "Default")
      (node (ref "C17") (pin "2") (pinfunction "2_2") (pintype "input"))
      (node (ref "R33") (pin "1") (pinfunction "1_1") (pintype "input"))
      (node (ref "R34") (pin "2") (pinfunction "2_2") (pintype "input"))
      (node (ref "R41") (pin "1") (pinfunction "1_1") (pintype "input"))
    )
    (net (code "15") (name "Net-(C20-Pad1)") (class "Default")
      (node (ref "C20") (pin "1") (pinfunction "1_1") (pintype "input"))
      (node (ref "R31") (pin "2") (pinfunction "2_2") (pintype "input"))
    )
    (net (code "16") (name "Net-(C22-Pad1)") (class "Default")
      (node (ref "C22") (pin "1") (pinfunction "1_1") (pintype "input"))
      (node (ref "R35") (pin "2") (pinfunction "2_2") (pintype "input"))
    )
    (net (code "17") (name "Net-(CN1-Pad1)") (class "Default")
      (node (ref "CN1") (pin "1") (pinfunction "1_1") (pintype "input"))
      (node (ref "R13") (pin "2") (pinfunction "2_2") (pintype "input"))
    )
    (net (code "18") (name "Net-(CN1-Pad2)") (class "Default")
      (node (ref "CN1") (pin "2") (pinfunction "2_2") (pintype "input"))
      (node (ref "R14") (pin "2") (pinfunction "2_2") (pintype "input"))
    )
    (net (code "19") (name "Net-(H5-Pad1)") (class "Default")
      (node (ref "H5") (pin "1") (pinfunction "1_1") (pintype "input"))
      (node (ref "SW3") (pin "2") (pinfunction "2_2") (pintype "input"))
    )
    (net (code "20") (name "Net-(LED1-C)") (class "Default")
      (node (ref "LED1") (pin "1") (pinfunction "C_1") (pintype "input"))
      (node (ref "R38") (pin "1") (pinfunction "1_1") (pintype "input"))
    )
    (net (code "21") (name "Net-(Q2-G)") (class "Default")
      (node (ref "Q2") (pin "1") (pinfunction "G_1") (pintype "input"))
      (node (ref "R23") (pin "2") (pinfunction "2_2") (pintype "input"))
      (node (ref "R29") (pin "1") (pinfunction "1_1") (pintype "input"))
    )
    (net (code "22") (name "Net-(Q3-G)") (class "Default")
      (node (ref "Q3") (pin "1") (pinfunction "G_1") (pintype "input"))
      (node (ref "R39") (pin "1") (pinfunction "1_1") (pintype "input"))
      (node (ref "R40") (pin "2") (pinfunction "2_2") (pintype "input"))
    )
    (net (code "23") (name "Net-(S1-ADDR)") (class "Default")
      (node (ref "R26") (pin "1") (pinfunction "1_1") (pintype "input"))
      (node (ref "S1") (pin "2") (pinfunction "ADDR_2") (pintype "input"))
    )
    (net (code "24") (name "Net-(U3-ADDR)") (class "Default")
      (node (ref "R27") (pin "1") (pinfunction "1_1") (pintype "input"))
      (node (ref "U3") (pin "2") (pinfunction "ADDR_2") (pintype "input"))
    )
    (net (code "25") (name "Net-(U3-DVI)") (class "Default")
      (node (ref "C14") (pin "2") (pinfunction "2_2") (pintype "input"))
      (node (ref "R28") (pin "1") (pinfunction "1_1") (pintype "input"))
      (node (ref "U3") (pin "5") (pinfunction "DVI_5") (pintype "input"))
    )
    (net (code "26") (name "Net-(U4-VINA+)") (class "Default")
      (node (ref "C26") (pin "2") (pinfunction "2_2") (pintype "input"))
      (node (ref "R41") (pin "2") (pinfunction "2_2") (pintype "input"))
      (node (ref "U4") (pin "3") (pinfunction "VINA+_3") (pintype "input"))
    )
    (net (code "27") (name "Net-(U4-VINA-)") (class "Default")
      (node (ref "R30") (pin "1") (pinfunction "1_1") (pintype "input"))
      (node (ref "R31") (pin "1") (pinfunction "1_1") (pintype "input"))
      (node (ref "U4") (pin "2") (pinfunction "VINA-_2") (pintype "input"))
    )
    (net (code "28") (name "Net-(U4-VINB+)") (class "Default")
      (node (ref "R30") (pin "2") (pinfunction "2_2") (pintype "input"))
      (node (ref "U4") (pin "1") (pinfunction "VOUTA_1") (pintype "input"))
      (node (ref "U4") (pin "5") (pinfunction "VINB+_5") (pintype "input"))
    )
    (net (code "29") (name "Net-(U4-VINB-)") (class "Default")
      (node (ref "R35") (pin "1") (pinfunction "1_1") (pintype "input"))
      (node (ref "R36") (pin "2") (pinfunction "2_2") (pintype "input"))
      (node (ref "U4") (pin "6") (pinfunction "VINB-_6") (pintype "input"))
    )
    (net (code "30") (name "OSC_IN") (class "Default")
      (node (ref "C10") (pin "1") (pinfunction "1_1") (pintype "input"))
      (node (ref "U1") (pin "5") (pinfunction "PD0-OSC_IN_5") (pintype "input"))
      (node (ref "X2") (pin "2") (pinfunction "OSC2_2") (pintype "input"))
    )
    (net (code "31") (name "OSC_OUT") (class "Default")
      (node (ref "C11") (pin "1") (pinfunction "1_1") (pintype "input"))
      (node (ref "U1") (pin "6") (pinfunction "PD1-OSC_OUT_6") (pintype "input"))
      (node (ref "X2") (pin "1") (pinfunction "OSC1_1") (pintype "input"))
    )
    (net (code "32") (name "RTC_OSC_IN") (class "Default")
      (node (ref "C9") (pin "1") (pinfunction "1_1") (pintype "input"))
      (node (ref "U1") (pin "3") (pinfunction "PC14-OSC32_IN_3") (pintype "input"))
      (node (ref "X1") (pin "2") (pinfunction "OSC2_2") (pintype "input"))
    )
    (net (code "33") (name "RTC_OSC_OUT") (class "Default")
      (node (ref "C8") (pin "1") (pinfunction "1_1") (pintype "input"))
      (node (ref "U1") (pin "4") (pinfunction "PC15-OSC32_OUT_4") (pintype "input"))
      (node (ref "X1") (pin "1") (pinfunction "OSC1_1") (pintype "input"))
    )
    (net (code "34") (name "SPI_MISO") (class "Default")
      (node (ref "U1") (pin "22") (pinfunction "PA6_22") (pintype "input"))
      (node (ref "U7") (pin "2") (pinfunction "DO_2") (pintype "input"))
    )
    (net (code "35") (name "SPI_MOSI") (class "Default")
      (node (ref "U1") (pin "23") (pinfunction "PA7_23") (pintype "input"))
      (node (ref "U7") (pin "5") (pinfunction "DI_5") (pintype "input"))
    )
    (net (code "36") (name "SPI_SCK") (class "Default")
      (node (ref "U1") (pin "21") (pinfunction "PA5_21") (pintype "input"))
      (node (ref "U7") (pin "6") (pinfunction "CLK_6") (pintype "input"))
    )
    (net (code "37") (name "SWCLK") (class "Default")
      (node (ref "R13") (pin "1") (pinfunction "1_1") (pintype "input"))
      (node (ref "U1") (pin "49") (pinfunction "PA14_49") (pintype "input"))
    )
    (net (code "38") (name "SWDIO") (class "Default")
      (node (ref "R14") (pin "1") (pinfunction "1_1") (pintype "input"))
      (node (ref "U1") (pin "46") (pinfunction "PA13_46") (pintype "input"))
    )
    (net (code "39") (name "USART1_RX") (class "Default")
      (node (ref "CN2") (pin "3") (pinfunction "3_3") (pintype "input"))
      (node (ref "U1") (pin "43") (pinfunction "PA10_43") (pintype "input"))
    )
    (net (code "40") (name "USART1_TX") (class "Default")
      (node (ref "CN2") (pin "4") (pinfunction "4_4") (pintype "input"))
      (node (ref "U1") (pin "42") (pinfunction "PA9_42") (pintype "input"))
    )
    (net (code "41") (name "USB_DM") (class "Default")
      (node (ref "U1") (pin "44") (pinfunction "PA11_44") (pintype "input"))
      (node (ref "USB1") (pin "2") (pinfunction "D-_2") (pintype "input"))
    )
    (net (code "42") (name "USB_DP") (class "Default")
      (node (ref "R8") (pin "2") (pinfunction "2_2") (pintype "input"))
      (node (ref "U1") (pin "45") (pinfunction "PA12_45") (pintype "input"))
      (node (ref "USB1") (pin "3") (pinfunction "D+_3") (pintype "input"))
    )
    (net (code "43") (name "VBAT") (class "Default")
      (node (ref "B2") (pin "1") (pinfunction "1_1") (pintype "input"))
      (node (ref "U1") (pin "1") (pinfunction "VBAT_1") (pintype "input"))
    )
    (net (code "44") (name "VCC") (class "Default")
      (node (ref "C13") (pin "2") (pinfunction "2_2") (pintype "input"))
      (node (ref "C15") (pin "2") (pinfunction "2_2") (pintype "input"))
      (node (ref "C16") (pin "2") (pinfunction "2_2") (pintype "input"))
      (node (ref "C19") (pin "2") (pinfunction "2_2") (pintype "input"))
      (node (ref "MIC1") (pin "1") (pinfunction "VDD_1") (pintype "input"))
      (node (ref "Q3") (pin "3") (pinfunction "D_3") (pintype "input"))
      (node (ref "R24") (pin "2") (pinfunction "2_2") (pintype "input"))
      (node (ref "R25") (pin "2") (pinfunction "2_2") (pintype "input"))
      (node (ref "R28") (pin "2") (pinfunction "2_2") (pintype "input"))
      (node (ref "R33") (pin "2") (pinfunction "2_2") (pintype "input"))
      (node (ref "S1") (pin "5") (pinfunction "VDD_5") (pintype "input"))
      (node (ref "S1") (pin "6") (pinfunction "NRESET_6") (pintype "input"))
      (node (ref "U3") (pin "1") (pinfunction "VCC_1") (pintype "input"))
      (node (ref "U4") (pin "8") (pinfunction "VDD_8") (pintype "input"))
    )
    (net (code "45") (name "VCONT") (class "Default")
      (node (ref "R39") (pin "2") (pinfunction "2_2") (pintype "input"))
      (node (ref "U1") (pin "56") (pinfunction "PB4_56") (pintype "input"))
    )
    (net (code "46") (name "VIN") (class "Default")
      (node (ref "Q2") (pin "2") (pinfunction "S_2") (pintype "input"))
      (node (ref "SW3") (pin "1") (pinfunction "1_1") (pintype "input"))
    )
    (net (code "47") (name "unconnected-(S1-ALERT-Pad3)") (class "Default")
      (node (ref "S1") (pin "3") (pinfunction "ALERT_3") (pintype "input+no_connect"))
    )
    (net (code "48") (name "unconnected-(SW3-Pad3)") (class "Default")
      (node (ref "SW3") (pin "3") (pinfunction "3_3") (pintype "input+no_connect"))
    )
    (net (code "49") (name "unconnected-(SW3-Pad4)") (class "Default")
      (node (ref "SW3") (pin "4") (pinfunction "4_4") (pintype "input+no_connect"))
    )
    (net (code "50") (name "unconnected-(SW3-Pad5)") (class "Default")
      (node (ref "SW3") (pin "5") (pinfunction "5_5") (pintype "input+no_connect"))
    )
    (net (code "51") (name "unconnected-(U1-PA2-Pad16)") (class "Default")
      (node (ref "U1") (pin "16") (pinfunction "PA2_16") (pintype "input+no_connect"))
    )
    (net (code "52") (name "unconnected-(U1-PA3-Pad17)") (class "Default")
      (node (ref "U1") (pin "17") (pinfunction "PA3_17") (pintype "input+no_connect"))
    )
    (net (code "53") (name "unconnected-(U1-PA8-Pad41)") (class "Default")
      (node (ref "U1") (pin "41") (pinfunction "PA8_41") (pintype "input+no_connect"))
    )
    (net (code "54") (name "unconnected-(U1-PA15-Pad50)") (class "Default")
      (node (ref "U1") (pin "50") (pinfunction "PA15_50") (pintype "input+no_connect"))
    )
    (net (code "55") (name "unconnected-(U1-PB0-Pad26)") (class "Default")
      (node (ref "U1") (pin "26") (pinfunction "PB0_26") (pintype "input+no_connect"))
    )
    (net (code "56") (name "unconnected-(U1-PB1-Pad27)") (class "Default")
      (node (ref "U1") (pin "27") (pinfunction "PB1_27") (pintype "input+no_connect"))
    )
    (net (code "57") (name "unconnected-(U1-PB3-Pad55)") (class "Default")
      (node (ref "U1") (pin "55") (pinfunction "PB3_55") (pintype "input+no_connect"))
    )
    (net (code "58") (name "unconnected-(U1-PB8-Pad61)") (class "Default")
      (node (ref "U1") (pin "61") (pinfunction "PB8_61") (pintype "input+no_connect"))
    )
    (net (code "59") (name "unconnected-(U1-PB9-Pad62)") (class "Default")
      (node (ref "U1") (pin "62") (pinfunction "PB9_62") (pintype "input+no_connect"))
    )
    (net (code "60") (name "unconnected-(U1-PB10-Pad29)") (class "Default")
      (node (ref "U1") (pin "29") (pinfunction "PB10_29") (pintype "input+no_connect"))
    )
    (net (code "61") (name "unconnected-(U1-PB11-Pad30)") (class "Default")
      (node (ref "U1") (pin "30") (pinfunction "PB11_30") (pintype "input+no_connect"))
    )
    (net (code "62") (name "unconnected-(U1-PB12-Pad33)") (class "Default")
      (node (ref "U1") (pin "33") (pinfunction "PB12_33") (pintype "input+no_connect"))
    )
    (net (code "63") (name "unconnected-(U1-PB13-Pad34)") (class "Default")
      (node (ref "U1") (pin "34") (pinfunction "PB13_34") (pintype "input+no_connect"))
    )
    (net (code "64") (name "unconnected-(U1-PB14-Pad35)") (class "Default")
      (node (ref "U1") (pin "35") (pinfunction "PB14_35") (pintype "input+no_connect"))
    )
    (net (code "65") (name "unconnected-(U1-PB15-Pad36)") (class "Default")
      (node (ref "U1") (pin "36") (pinfunction "PB15_36") (pintype "input+no_connect"))
    )
    (net (code "66") (name "unconnected-(U1-PC0-Pad8)") (class "Default")
      (node (ref "U1") (pin "8") (pinfunction "PC0_8") (pintype "input+no_connect"))
    )
    (net (code "67") (name "unconnected-(U1-PC1-Pad9)") (class "Default")
      (node (ref "U1") (pin "9") (pinfunction "PC1_9") (pintype "input+no_connect"))
    )
    (net (code "68") (name "unconnected-(U1-PC2-Pad10)") (class "Default")
      (node (ref "U1") (pin "10") (pinfunction "PC2_10") (pintype "input+no_connect"))
    )
    (net (code "69") (name "unconnected-(U1-PC3-Pad11)") (class "Default")
      (node (ref "U1") (pin "11") (pinfunction "PC3_11") (pintype "input+no_connect"))
    )
    (net (code "70") (name "unconnected-(U1-PC4-Pad24)") (class "Default")
      (node (ref "U1") (pin "24") (pinfunction "PC4_24") (pintype "input+no_connect"))
    )
    (net (code "71") (name "unconnected-(U1-PC5-Pad25)") (class "Default")
      (node (ref "U1") (pin "25") (pinfunction "PC5_25") (pintype "input+no_connect"))
    )
    (net (code "72") (name "unconnected-(U1-PC6-Pad37)") (class "Default")
      (node (ref "U1") (pin "37") (pinfunction "PC6_37") (pintype "input+no_connect"))
    )
    (net (code "73") (name "unconnected-(U1-PC7-Pad38)") (class "Default")
      (node (ref "U1") (pin "38") (pinfunction "PC7_38") (pintype "input+no_connect"))
    )
    (net (code "74") (name "unconnected-(U1-PC8-Pad39)") (class "Default")
      (node (ref "U1") (pin "39") (pinfunction "PC8_39") (pintype "input+no_connect"))
    )
    (net (code "75") (name "unconnected-(U1-PC9-Pad40)") (class "Default")
      (node (ref "U1") (pin "40") (pinfunction "PC9_40") (pintype "input+no_connect"))
    )
    (net (code "76") (name "unconnected-(U1-PC10-Pad51)") (class "Default")
      (node (ref "U1") (pin "51") (pinfunction "PC10_51") (pintype "input+no_connect"))
    )
    (net (code "77") (name "unconnected-(U1-PC11-Pad52)") (class "Default")
      (node (ref "U1") (pin "52") (pinfunction "PC11_52") (pintype "input+no_connect"))
    )
    (net (code "78") (name "unconnected-(U1-PC12-Pad53)") (class "Default")
      (node (ref "U1") (pin "53") (pinfunction "PC12_53") (pintype "input+no_connect"))
    )
    (net (code "79") (name "unconnected-(U1-PC13-TAMPER-RTC-Pad2)") (class "Default")
      (node (ref "U1") (pin "2") (pinfunction "PC13-TAMPER-RTC_2") (pintype "input+no_connect"))
    )
    (net (code "80") (name "unconnected-(U1-PD2-Pad54)") (class "Default")
      (node (ref "U1") (pin "54") (pinfunction "PD2_54") (pintype "input+no_connect"))
    )
    (net (code "81") (name "unconnected-(USB1-ID-Pad4)") (class "Default")
      (node (ref "USB1") (pin "4") (pinfunction "ID_4") (pintype "input+no_connect"))
    )
  )
)
